# rapidshark-lipo-sensor-mk-3_0.net
KiCad netlist of a schematic drawn in EAGLE
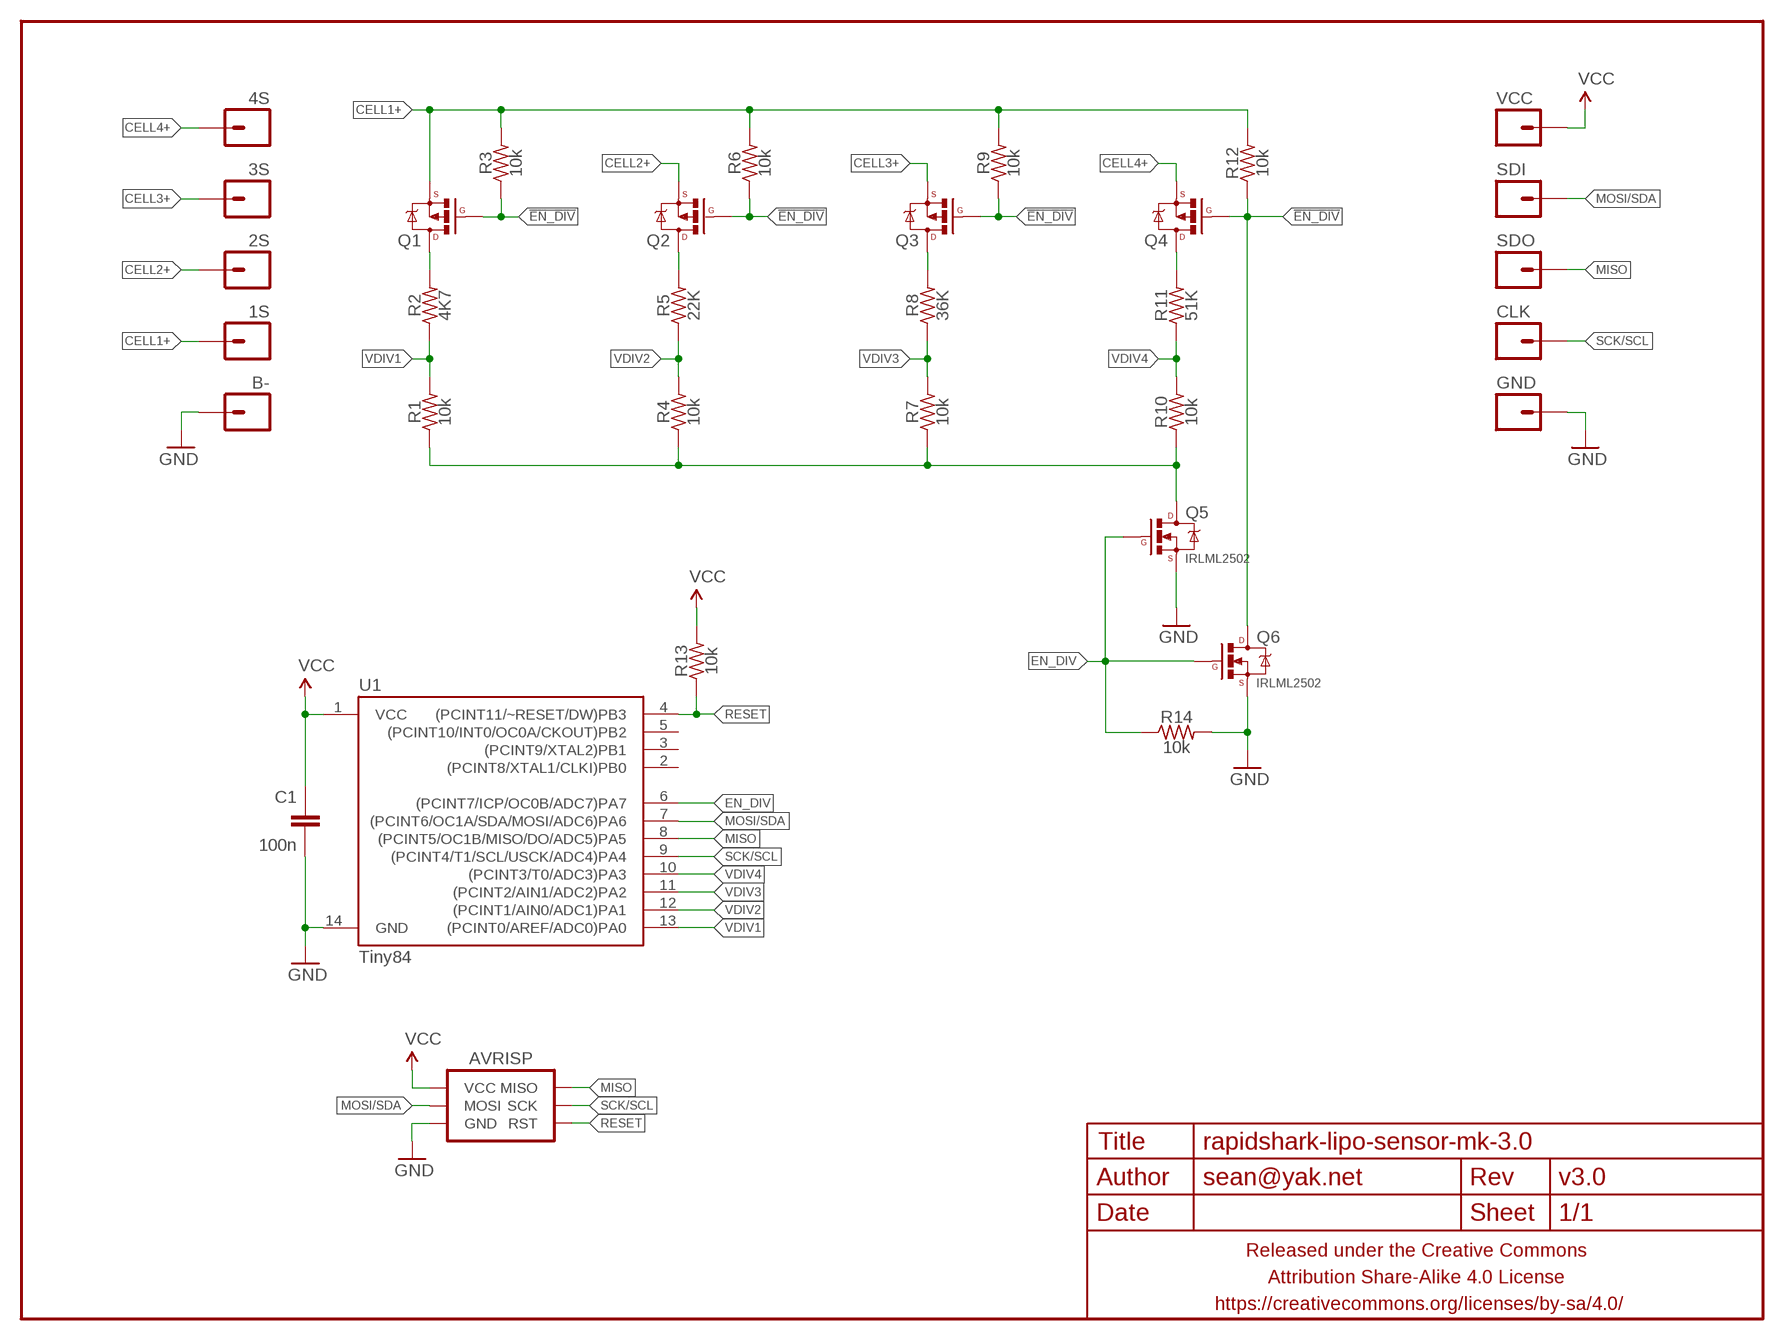
[diagram p0: schematic, sheet 1]

(export (version "E")
  (design (tool "Eeschema 10.0.6"))
  (components
    (comp (ref "1S")
      (value "M01PTH-0.9MM")
      (footprint "eagle-import:1X01-0.9MM")
      (libsource (lib "eagle-import") (part "M01PTH-0.9MM"))
    )
    (comp (ref "2S")
      (value "M01PTH-0.9MM")
      (footprint "eagle-import:1X01-0.9MM")
      (libsource (lib "eagle-import") (part "M01PTH-0.9MM"))
    )
    (comp (ref "3S")
      (value "M01PTH-0.9MM")
      (footprint "eagle-import:1X01-0.9MM")
      (libsource (lib "eagle-import") (part "M01PTH-0.9MM"))
    )
    (comp (ref "4S")
      (value "M01PTH-0.9MM")
      (footprint "eagle-import:1X01-0.9MM")
      (libsource (lib "eagle-import") (part "M01PTH-0.9MM"))
    )
    (comp (ref "AVRISP")
      (value "AVR_SPI_PRG_6SMD_TEST_POINTS")
      (footprint "eagle-import:2X3_SMD_TEST_POINTS")
      (libsource (lib "eagle-import") (part "AVR_SPI_PRG_6SMD_TEST_POINTS"))
    )
    (comp (ref "B-")
      (value "M01PTH-0.9MM")
      (footprint "eagle-import:1X01-0.9MM")
      (libsource (lib "eagle-import") (part "M01PTH-0.9MM"))
    )
    (comp (ref "C1")
      (value "100n")
      (footprint "eagle-import:C0603-TIGHTER")
      (libsource (lib "eagle-import") (part "CAPACITOR-CERAMICC0603-TIGHTER"))
    )
    (comp (ref "CLK")
      (value "M01PTH-0.9MM")
      (footprint "eagle-import:1X01-0.9MM")
      (libsource (lib "eagle-import") (part "M01PTH-0.9MM"))
    )
    (comp (ref "FRAME1")
      (value "FRAME-LETTERNO_PACKAGE")
      (footprint "eagle-import:DUMMY")
      (fields (field (name "DESIGNER") "sean@yak.net") (field (name "VERSION") "v3.0"))
      (libsource (lib "eagle-import") (part "FRAME-LETTERNO_PACKAGE"))
    )
    (comp (ref "GND")
      (value "M01PTH-0.9MM")
      (footprint "eagle-import:1X01-0.9MM")
      (libsource (lib "eagle-import") (part "M01PTH-0.9MM"))
    )
    (comp (ref "Q1")
      (value "MOSFET-PCHANNELSOT-23")
      (footprint "eagle-import:SOT23")
      (libsource (lib "eagle-import") (part "MOSFET-PCHANNELSOT-23"))
    )
    (comp (ref "Q2")
      (value "MOSFET-PCHANNELSOT-23")
      (footprint "eagle-import:SOT23")
      (libsource (lib "eagle-import") (part "MOSFET-PCHANNELSOT-23"))
    )
    (comp (ref "Q3")
      (value "MOSFET-PCHANNELSOT-23")
      (footprint "eagle-import:SOT23")
      (libsource (lib "eagle-import") (part "MOSFET-PCHANNELSOT-23"))
    )
    (comp (ref "Q4")
      (value "MOSFET-PCHANNELSOT-23")
      (footprint "eagle-import:SOT23")
      (libsource (lib "eagle-import") (part "MOSFET-PCHANNELSOT-23"))
    )
    (comp (ref "Q5")
      (value "IRLML2502")
      (footprint "eagle-import:SOT23")
      (libsource (lib "eagle-import") (part "MOSFET-NCHANNELIRLML2502"))
    )
    (comp (ref "Q6")
      (value "IRLML2502")
      (footprint "eagle-import:SOT23")
      (libsource (lib "eagle-import") (part "MOSFET-NCHANNELIRLML2502"))
    )
    (comp (ref "R1")
      (value "10k")
      (footprint "eagle-import:R0603-TIGHTER")
      (libsource (lib "eagle-import") (part "RESISTORR0603-TIGHTER"))
    )
    (comp (ref "R2")
      (value "4K7")
      (footprint "eagle-import:R0603-TIGHTER")
      (libsource (lib "eagle-import") (part "RESISTORR0603-TIGHTER"))
    )
    (comp (ref "R3")
      (value "10k")
      (footprint "eagle-import:R0603-TIGHTER")
      (libsource (lib "eagle-import") (part "RESISTORR0603-TIGHTER"))
    )
    (comp (ref "R4")
      (value "10k")
      (footprint "eagle-import:R0603-TIGHTER")
      (libsource (lib "eagle-import") (part "RESISTORR0603-TIGHTER"))
    )
    (comp (ref "R5")
      (value "22K")
      (footprint "eagle-import:R0603-TIGHTER")
      (libsource (lib "eagle-import") (part "RESISTORR0603-TIGHTER"))
    )
    (comp (ref "R6")
      (value "10k")
      (footprint "eagle-import:R0603-TIGHTER")
      (libsource (lib "eagle-import") (part "RESISTORR0603-TIGHTER"))
    )
    (comp (ref "R7")
      (value "10k")
      (footprint "eagle-import:R0603-TIGHTER")
      (libsource (lib "eagle-import") (part "RESISTORR0603-TIGHTER"))
    )
    (comp (ref "R8")
      (value "36K")
      (footprint "eagle-import:R0603-TIGHTER")
      (libsource (lib "eagle-import") (part "RESISTORR0603-TIGHTER"))
    )
    (comp (ref "R9")
      (value "10k")
      (footprint "eagle-import:R0603-TIGHTER")
      (libsource (lib "eagle-import") (part "RESISTORR0603-TIGHTER"))
    )
    (comp (ref "R10")
      (value "10k")
      (footprint "eagle-import:R0603-TIGHTER")
      (libsource (lib "eagle-import") (part "RESISTORR0603-TIGHTER"))
    )
    (comp (ref "R11")
      (value "51K")
      (footprint "eagle-import:R0603-TIGHTER")
      (libsource (lib "eagle-import") (part "RESISTORR0603-TIGHTER"))
    )
    (comp (ref "R12")
      (value "10k")
      (footprint "eagle-import:R0603-TIGHTER")
      (libsource (lib "eagle-import") (part "RESISTORR0603-TIGHTER"))
    )
    (comp (ref "R13")
      (value "10k")
      (footprint "eagle-import:R0603-TIGHTER")
      (libsource (lib "eagle-import") (part "RESISTORR0603-TIGHTER"))
    )
    (comp (ref "R14")
      (value "10k")
      (footprint "eagle-import:R0603-TIGHTER")
      (libsource (lib "eagle-import") (part "RESISTORR0603-TIGHTER"))
    )
    (comp (ref "SDI")
      (value "M01PTH-0.9MM")
      (footprint "eagle-import:1X01-0.9MM")
      (libsource (lib "eagle-import") (part "M01PTH-0.9MM"))
    )
    (comp (ref "SDO")
      (value "M01PTH-0.9MM")
      (footprint "eagle-import:1X01-0.9MM")
      (libsource (lib "eagle-import") (part "M01PTH-0.9MM"))
    )
    (comp (ref "U1")
      (value "Tiny84")
      (footprint "eagle-import:SO14")
      (libsource (lib "eagle-import") (part "ATTINY84"))
    )
    (comp (ref "VCC")
      (value "M01PTH-0.9MM")
      (footprint "eagle-import:1X01-0.9MM")
      (libsource (lib "eagle-import") (part "M01PTH-0.9MM"))
    )
  )
  (nets
    (net (code "1") (name "/~{EN_DIV}") (class "Default")
      (node (ref "Q1") (pin "1") (pinfunction "G_1") (pintype "passive"))
      (node (ref "Q2") (pin "1") (pinfunction "G_1") (pintype "passive"))
      (node (ref "Q3") (pin "1") (pinfunction "G_1") (pintype "passive"))
      (node (ref "Q4") (pin "1") (pinfunction "G_1") (pintype "passive"))
      (node (ref "Q6") (pin "3") (pinfunction "D_3") (pintype "passive"))
      (node (ref "R12") (pin "1") (pinfunction "1_1") (pintype "passive"))
      (node (ref "R3") (pin "1") (pinfunction "1_1") (pintype "passive"))
      (node (ref "R6") (pin "1") (pinfunction "1_1") (pintype "passive"))
      (node (ref "R9") (pin "1") (pinfunction "1_1") (pintype "passive"))
    )
    (net (code "2") (name "CELL1+") (class "Default")
      (node (ref "1S") (pin "1") (pinfunction "1_1") (pintype "passive"))
      (node (ref "Q1") (pin "2") (pinfunction "S_2") (pintype "passive"))
      (node (ref "R12") (pin "2") (pinfunction "2_2") (pintype "passive"))
      (node (ref "R3") (pin "2") (pinfunction "2_2") (pintype "passive"))
      (node (ref "R6") (pin "2") (pinfunction "2_2") (pintype "passive"))
      (node (ref "R9") (pin "2") (pinfunction "2_2") (pintype "passive"))
    )
    (net (code "3") (name "CELL2+") (class "Default")
      (node (ref "2S") (pin "1") (pinfunction "1_1") (pintype "passive"))
      (node (ref "Q2") (pin "2") (pinfunction "S_2") (pintype "passive"))
    )
    (net (code "4") (name "CELL3+") (class "Default")
      (node (ref "3S") (pin "1") (pinfunction "1_1") (pintype "passive"))
      (node (ref "Q3") (pin "2") (pinfunction "S_2") (pintype "passive"))
    )
    (net (code "5") (name "CELL4+") (class "Default")
      (node (ref "4S") (pin "1") (pinfunction "1_1") (pintype "passive"))
      (node (ref "Q4") (pin "2") (pinfunction "S_2") (pintype "passive"))
    )
    (net (code "6") (name "EN_DIV") (class "Default")
      (node (ref "Q5") (pin "1") (pinfunction "G_1") (pintype "passive"))
      (node (ref "Q6") (pin "1") (pinfunction "G_1") (pintype "passive"))
      (node (ref "R14") (pin "1") (pinfunction "1_1") (pintype "passive"))
      (node (ref "U1") (pin "6") (pinfunction "(PCINT7/ICP/OC0B/ADC7)PA7_6") (pintype "bidirectional"))
    )
    (net (code "7") (name "GND") (class "Default")
      (node (ref "AVRISP") (pin "6") (pinfunction "GND_6") (pintype "passive"))
      (node (ref "B-") (pin "1") (pinfunction "1_1") (pintype "passive"))
      (node (ref "C1") (pin "2") (pinfunction "2_2") (pintype "passive"))
      (node (ref "GND") (pin "1") (pinfunction "1_1") (pintype "passive"))
      (node (ref "Q5") (pin "2") (pinfunction "S_2") (pintype "passive"))
      (node (ref "Q6") (pin "2") (pinfunction "S_2") (pintype "passive"))
      (node (ref "R14") (pin "2") (pinfunction "2_2") (pintype "passive"))
      (node (ref "U1") (pin "14") (pinfunction "GND_14") (pintype "bidirectional"))
    )
    (net (code "8") (name "MISO") (class "Default")
      (node (ref "AVRISP") (pin "1") (pinfunction "MISO_1") (pintype "passive"))
      (node (ref "SDO") (pin "1") (pinfunction "1_1") (pintype "passive"))
      (node (ref "U1") (pin "8") (pinfunction "(PCINT5/OC1B/MISO/DO/ADC5)PA5_8") (pintype "bidirectional"))
    )
    (net (code "9") (name "MOSI{slash}SDA") (class "Default")
      (node (ref "AVRISP") (pin "4") (pinfunction "MOSI_4") (pintype "passive"))
      (node (ref "SDI") (pin "1") (pinfunction "1_1") (pintype "passive"))
      (node (ref "U1") (pin "7") (pinfunction "(PCINT6/OC1A/SDA/MOSI/ADC6)PA6_7") (pintype "bidirectional"))
    )
    (net (code "10") (name "Net-(Q1-D)") (class "Default")
      (node (ref "Q1") (pin "3") (pinfunction "D_3") (pintype "passive"))
      (node (ref "R2") (pin "2") (pinfunction "2_2") (pintype "passive"))
    )
    (net (code "11") (name "Net-(Q2-D)") (class "Default")
      (node (ref "Q2") (pin "3") (pinfunction "D_3") (pintype "passive"))
      (node (ref "R5") (pin "2") (pinfunction "2_2") (pintype "passive"))
    )
    (net (code "12") (name "Net-(Q3-D)") (class "Default")
      (node (ref "Q3") (pin "3") (pinfunction "D_3") (pintype "passive"))
      (node (ref "R8") (pin "2") (pinfunction "2_2") (pintype "passive"))
    )
    (net (code "13") (name "Net-(Q4-D)") (class "Default")
      (node (ref "Q4") (pin "3") (pinfunction "D_3") (pintype "passive"))
      (node (ref "R11") (pin "2") (pinfunction "2_2") (pintype "passive"))
    )
    (net (code "14") (name "Net-(Q5-D)") (class "Default")
      (node (ref "Q5") (pin "3") (pinfunction "D_3") (pintype "passive"))
      (node (ref "R1") (pin "1") (pinfunction "1_1") (pintype "passive"))
      (node (ref "R10") (pin "1") (pinfunction "1_1") (pintype "passive"))
      (node (ref "R4") (pin "1") (pinfunction "1_1") (pintype "passive"))
      (node (ref "R7") (pin "1") (pinfunction "1_1") (pintype "passive"))
    )
    (net (code "15") (name "RESET") (class "Default")
      (node (ref "AVRISP") (pin "5") (pinfunction "RST_5") (pintype "passive"))
      (node (ref "R13") (pin "1") (pinfunction "1_1") (pintype "passive"))
      (node (ref "U1") (pin "4") (pinfunction "(PCINT11/~{RESET/DW})PB3_4") (pintype "bidirectional"))
    )
    (net (code "16") (name "SCK{slash}SCL") (class "Default")
      (node (ref "AVRISP") (pin "3") (pinfunction "SCK_3") (pintype "passive"))
      (node (ref "CLK") (pin "1") (pinfunction "1_1") (pintype "passive"))
      (node (ref "U1") (pin "9") (pinfunction "(PCINT4/T1/SCL/USCK/ADC4)PA4_9") (pintype "bidirectional"))
    )
    (net (code "17") (name "VCC") (class "Default")
      (node (ref "AVRISP") (pin "2") (pinfunction "VCC_2") (pintype "passive"))
      (node (ref "C1") (pin "1") (pinfunction "1_1") (pintype "passive"))
      (node (ref "R13") (pin "2") (pinfunction "2_2") (pintype "passive"))
      (node (ref "U1") (pin "1") (pinfunction "VCC_1") (pintype "bidirectional"))
      (node (ref "VCC") (pin "1") (pinfunction "1_1") (pintype "passive"))
    )
    (net (code "18") (name "VDIV1") (class "Default")
      (node (ref "R1") (pin "2") (pinfunction "2_2") (pintype "passive"))
      (node (ref "R2") (pin "1") (pinfunction "1_1") (pintype "passive"))
      (node (ref "U1") (pin "13") (pinfunction "(PCINT0/AREF/ADC0)PA0_13") (pintype "bidirectional"))
    )
    (net (code "19") (name "VDIV2") (class "Default")
      (node (ref "R4") (pin "2") (pinfunction "2_2") (pintype "passive"))
      (node (ref "R5") (pin "1") (pinfunction "1_1") (pintype "passive"))
      (node (ref "U1") (pin "12") (pinfunction "(PCINT1/AIN0/ADC1)PA1_12") (pintype "bidirectional"))
    )
    (net (code "20") (name "VDIV3") (class "Default")
      (node (ref "R7") (pin "2") (pinfunction "2_2") (pintype "passive"))
      (node (ref "R8") (pin "1") (pinfunction "1_1") (pintype "passive"))
      (node (ref "U1") (pin "11") (pinfunction "(PCINT2/AIN1/ADC2)PA2_11") (pintype "bidirectional"))
    )
    (net (code "21") (name "VDIV4") (class "Default")
      (node (ref "R10") (pin "2") (pinfunction "2_2") (pintype "passive"))
      (node (ref "R11") (pin "1") (pinfunction "1_1") (pintype "passive"))
      (node (ref "U1") (pin "10") (pinfunction "(PCINT3/T0/ADC3)PA3_10") (pintype "bidirectional"))
    )
    (net (code "22") (name "unconnected-(U1-(PCINT8{slash}XTAL1{slash}CLKI)PB0-Pad2)") (class "Default")
      (node (ref "U1") (pin "2") (pinfunction "(PCINT8/XTAL1/CLKI)PB0_2") (pintype "bidirectional"))
    )
    (net (code "23") (name "unconnected-(U1-(PCINT9{slash}XTAL2)PB1-Pad3)") (class "Default")
      (node (ref "U1") (pin "3") (pinfunction "(PCINT9/XTAL2)PB1_3") (pintype "bidirectional"))
    )
    (net (code "24") (name "unconnected-(U1-(PCINT10{slash}INT0{slash}OC0A{slash}CKOUT)PB2-Pad5)") (class "Default")
      (node (ref "U1") (pin "5") (pinfunction "(PCINT10/INT0/OC0A/CKOUT)PB2_5") (pintype "bidirectional"))
    )
  )
)
